# CON_HDMI_TYPEA.net
KiCad netlist of a schematic drawn in Altium Designer
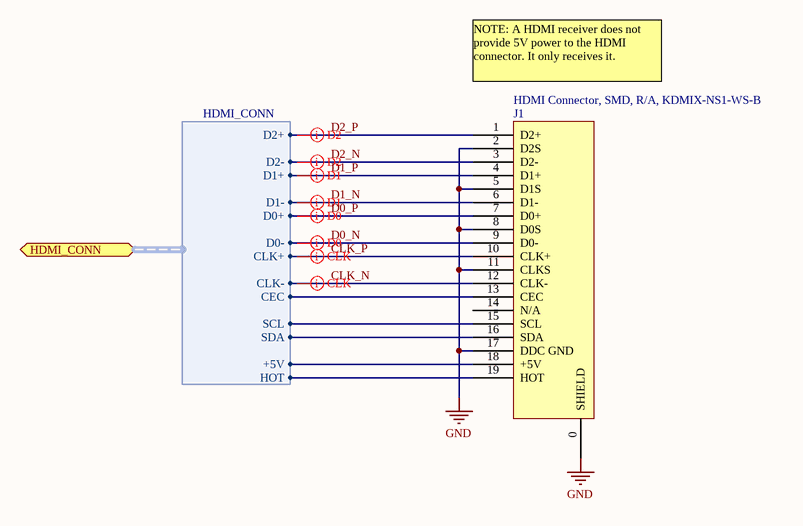
[diagram p0: CON_HDMI_TYPEA.SchDoc]

(export (version "E")
  (design (tool "Eeschema 10.0.6"))
  (components
    (comp (ref "J1")
      (value "HDMI Connector, SMD, R/A, KDMIX-NS1-WS-B")
      (footprint "HDMI-RA-Kycon")
      (description "HDMI, SMD, R/A KDMIX-NS1-WS-B")
      (libsource (lib "AltiumDesignLibrary") (part "HDMI-RA-Kycon"))
    )
  )
  (nets
    (net (code "2") (name "/+5V") (class "Default")
      (node (ref "J1") (pin "18") (pinfunction "+5V_18") (pintype "passive"))
    )
    (net (code "3") (name "/CEC") (class "Default")
      (node (ref "J1") (pin "13") (pinfunction "CEC_13") (pintype "passive"))
    )
    (net (code "4") (name "/CLK_N") (class "Default")
      (node (ref "J1") (pin "12") (pinfunction "CLK-_12") (pintype "passive"))
    )
    (net (code "5") (name "/CLK_P") (class "Default")
      (node (ref "J1") (pin "10") (pinfunction "CLK+_10") (pintype "passive"))
    )
    (net (code "6") (name "/D0_N") (class "Default")
      (node (ref "J1") (pin "9") (pinfunction "D0-_9") (pintype "passive"))
    )
    (net (code "7") (name "/D0_P") (class "Default")
      (node (ref "J1") (pin "7") (pinfunction "D0+_7") (pintype "passive"))
    )
    (net (code "8") (name "/D1_N") (class "Default")
      (node (ref "J1") (pin "6") (pinfunction "D1-_6") (pintype "passive"))
    )
    (net (code "9") (name "/D1_P") (class "Default")
      (node (ref "J1") (pin "4") (pinfunction "D1+_4") (pintype "passive"))
    )
    (net (code "10") (name "/D2_N") (class "Default")
      (node (ref "J1") (pin "3") (pinfunction "D2-_3") (pintype "passive"))
    )
    (net (code "11") (name "/D2_P") (class "Default")
      (node (ref "J1") (pin "1") (pinfunction "D2+_1") (pintype "passive"))
    )
    (net (code "12") (name "/HOT") (class "Default")
      (node (ref "J1") (pin "19") (pinfunction "HOT_19") (pintype "passive"))
    )
    (net (code "13") (name "/SCL") (class "Default")
      (node (ref "J1") (pin "15") (pinfunction "SCL_15") (pintype "passive"))
    )
    (net (code "14") (name "/SDA") (class "Default")
      (node (ref "J1") (pin "16") (pinfunction "SDA_16") (pintype "passive"))
    )
    (net (code "16") (name "GND") (class "Default")
      (node (ref "J1") (pin "0") (pinfunction "SHIELD_0") (pintype "passive"))
      (node (ref "J1") (pin "11") (pinfunction "CLKS_11") (pintype "passive"))
      (node (ref "J1") (pin "17") (pinfunction "DDC_GND_17") (pintype "passive"))
      (node (ref "J1") (pin "2") (pinfunction "D2S_2") (pintype "passive"))
      (node (ref "J1") (pin "5") (pinfunction "D1S_5") (pintype "passive"))
      (node (ref "J1") (pin "8") (pinfunction "D0S_8") (pintype "passive"))
    )
    (net (code "17") (name "unconnected-(J1-N{slash}A-Pad14)") (class "Default")
      (node (ref "J1") (pin "14") (pinfunction "N/A_14") (pintype "passive"))
    )
  )
)
